# LoRa_1W_Breakout_868MHz.net
KiCad netlist of a schematic drawn in EAGLE
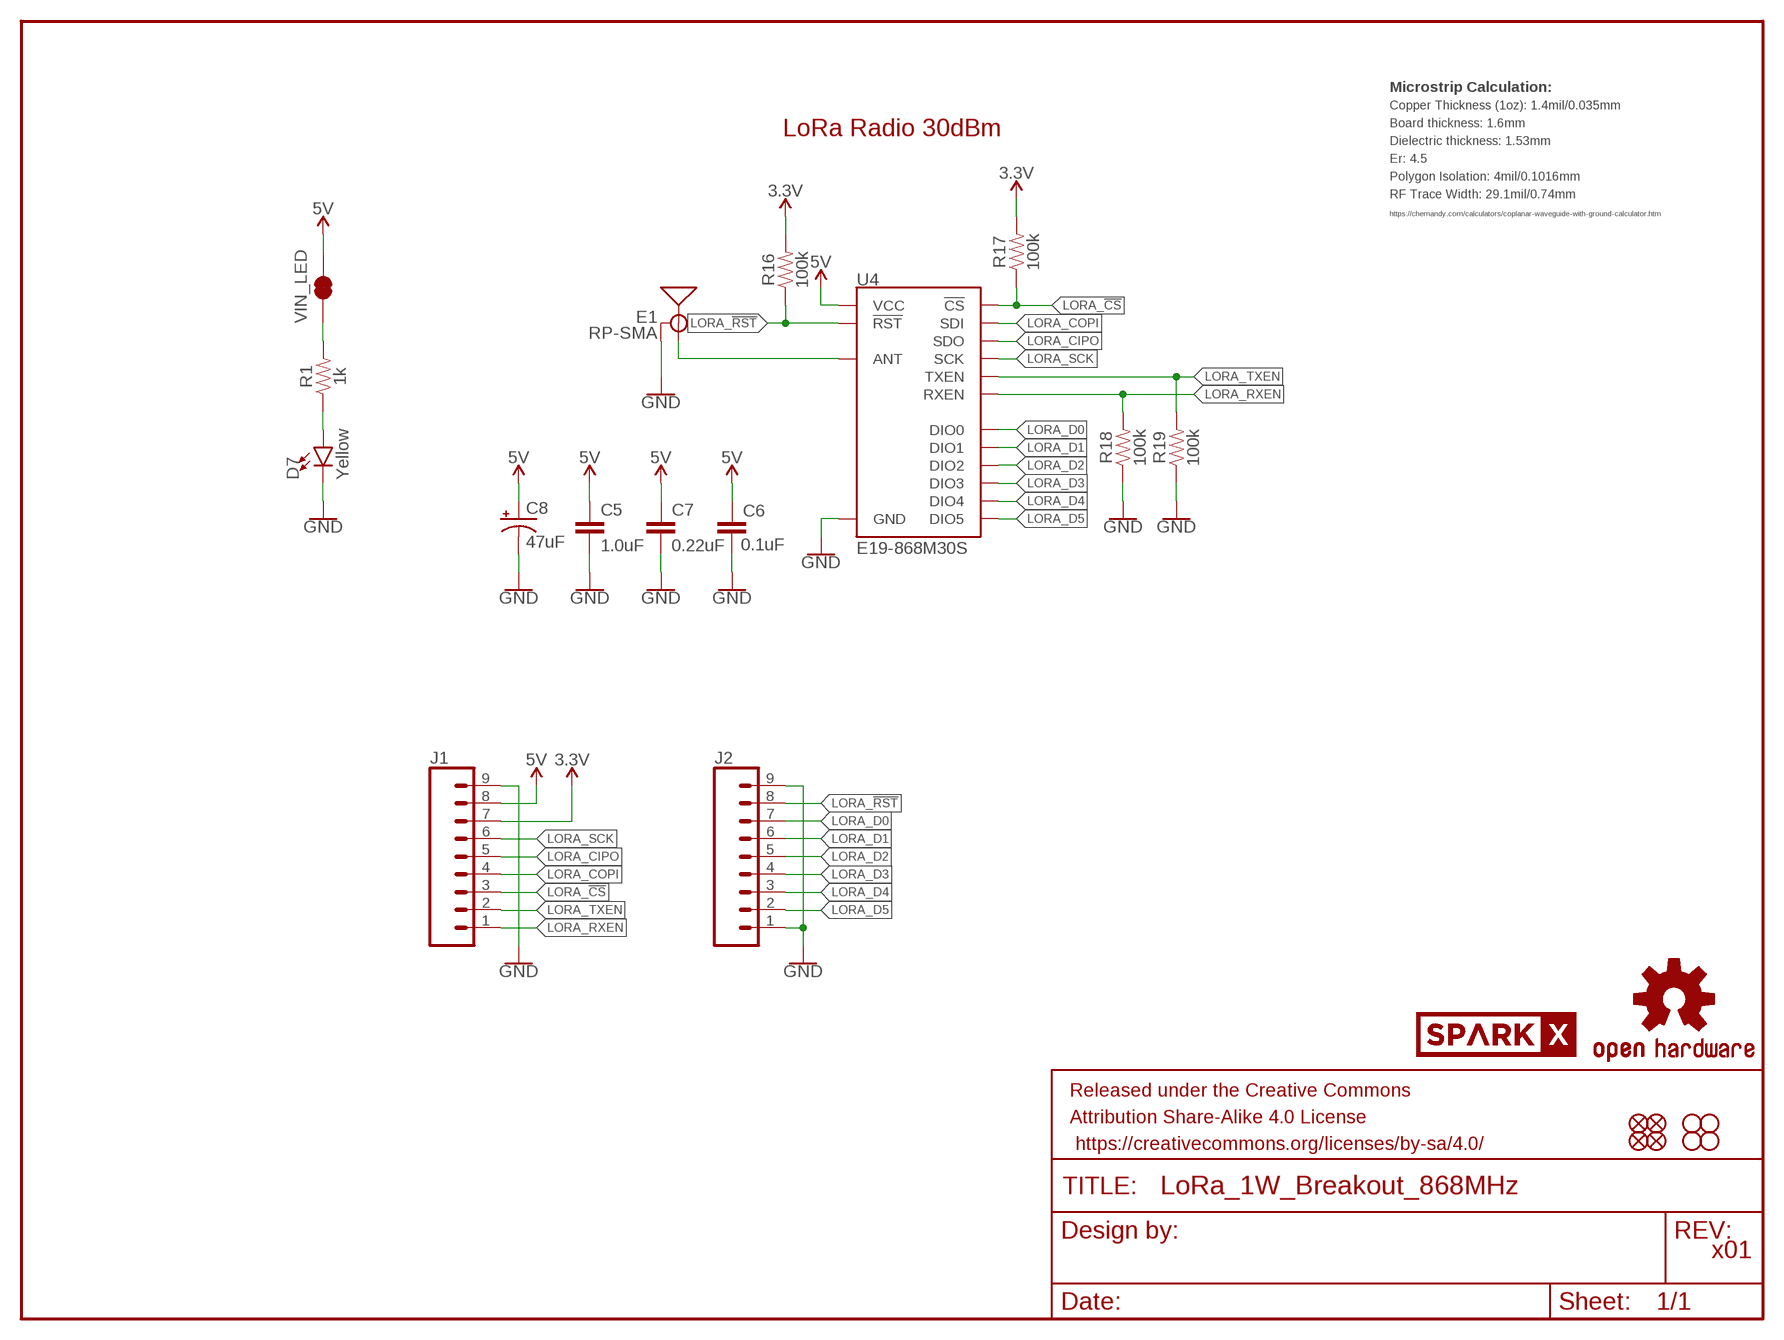
[diagram p0: schematic, sheet 1]

(export (version "E")
  (design (tool "Eeschema 10.0.6"))
  (components
    (comp (ref "C5")
      (value "1.0uF")
      (footprint "eagle-import:0603")
      (libsource (lib "eagle-import") (part "1.0UF-0603-16V-10%"))
    )
    (comp (ref "C6")
      (value "0.1uF")
      (footprint "eagle-import:0603")
      (libsource (lib "eagle-import") (part "0.1UF-0603-25V-(+80/-20%)"))
    )
    (comp (ref "C7")
      (value "0.22uF")
      (footprint "eagle-import:0603")
      (libsource (lib "eagle-import") (part "0.22UF-0603-25V-10%"))
    )
    (comp (ref "C8")
      (value "47uF")
      (footprint "eagle-import:EIA3528")
      (libsource (lib "eagle-import") (part "47UF-POLAR-EIA3528-10V-10%"))
    )
    (comp (ref "D7")
      (value "Yellow")
      (footprint "eagle-import:LED-0603")
      (libsource (lib "eagle-import") (part "LED-YELLOW0603"))
    )
    (comp (ref "E1")
      (value "RP-SMA")
      (footprint "eagle-import:SMA-EDGE")
      (libsource (lib "eagle-import") (part "ANTENNA-SMA-GROUNDEDEDGE_RPSMA"))
    )
    (comp (ref "FD1")
      (value "FIDUCIALUFIDUCIAL")
      (footprint "eagle-import:FIDUCIAL-MICRO")
      (libsource (lib "eagle-import") (part "FIDUCIALUFIDUCIAL"))
    )
    (comp (ref "FD2")
      (value "FIDUCIALUFIDUCIAL")
      (footprint "eagle-import:FIDUCIAL-MICRO")
      (libsource (lib "eagle-import") (part "FIDUCIALUFIDUCIAL"))
    )
    (comp (ref "FD3")
      (value "FIDUCIALUFIDUCIAL")
      (footprint "eagle-import:FIDUCIAL-MICRO")
      (libsource (lib "eagle-import") (part "FIDUCIALUFIDUCIAL"))
    )
    (comp (ref "FD4")
      (value "FIDUCIALUFIDUCIAL")
      (footprint "eagle-import:FIDUCIAL-MICRO")
      (libsource (lib "eagle-import") (part "FIDUCIALUFIDUCIAL"))
    )
    (comp (ref "FRAME2")
      (value "FRAME-LETTER")
      (footprint "eagle-import:CREATIVE_COMMONS")
      (libsource (lib "eagle-import") (part "FRAME-LETTER"))
    )
    (comp (ref "H1")
      (value "STAND-OFF")
      (footprint "eagle-import:STAND-OFF")
      (libsource (lib "eagle-import") (part "STAND-OFF"))
    )
    (comp (ref "H2")
      (value "STAND-OFF")
      (footprint "eagle-import:STAND-OFF")
      (libsource (lib "eagle-import") (part "STAND-OFF"))
    )
    (comp (ref "H3")
      (value "STAND-OFF")
      (footprint "eagle-import:STAND-OFF")
      (libsource (lib "eagle-import") (part "STAND-OFF"))
    )
    (comp (ref "H4")
      (value "STAND-OFF")
      (footprint "eagle-import:STAND-OFF")
      (libsource (lib "eagle-import") (part "STAND-OFF"))
    )
    (comp (ref "J1")
      (value "CONN_09NO_SILK")
      (footprint "eagle-import:1X09_NO_SILK")
      (libsource (lib "eagle-import") (part "CONN_09NO_SILK"))
    )
    (comp (ref "J2")
      (value "CONN_09NO_SILK")
      (footprint "eagle-import:1X09_NO_SILK")
      (libsource (lib "eagle-import") (part "CONN_09NO_SILK"))
    )
    (comp (ref "LOGO3")
      (value "OSHW-LOGOMINI")
      (footprint "eagle-import:OSHW-LOGO-MINI")
      (libsource (lib "eagle-import") (part "OSHW-LOGOMINI"))
    )
    (comp (ref "R1")
      (value "1k")
      (footprint "eagle-import:0603")
      (libsource (lib "eagle-import") (part "1KOHM-0603-1/10W-1%"))
    )
    (comp (ref "R16")
      (value "100k")
      (footprint "eagle-import:0603")
      (libsource (lib "eagle-import") (part "100KOHM-0603-1/10W-1%"))
    )
    (comp (ref "R17")
      (value "100k")
      (footprint "eagle-import:0603")
      (libsource (lib "eagle-import") (part "100KOHM-0603-1/10W-1%"))
    )
    (comp (ref "R18")
      (value "100k")
      (footprint "eagle-import:0603")
      (libsource (lib "eagle-import") (part "100KOHM-0603-1/10W-1%"))
    )
    (comp (ref "R19")
      (value "100k")
      (footprint "eagle-import:0603")
      (libsource (lib "eagle-import") (part "100KOHM-0603-1/10W-1%"))
    )
    (comp (ref "U$5")
      (value "SPARKX-LOGO5")
      (footprint "eagle-import:SPARKX-LARGE")
      (libsource (lib "eagle-import") (part "SPARKX-LOGO5"))
    )
    (comp (ref "U4")
      (value "E19-868M30S")
      (footprint "eagle-import:E19-915M30S")
      (libsource (lib "eagle-import") (part "LORA-E19868MHZ"))
    )
    (comp (ref "VIN_LED")
      (value "JUMPER-SMT_2_NC_TRACE_SILK")
      (footprint "eagle-import:SMT-JUMPER_2_NC_TRACE_SILK")
      (libsource (lib "eagle-import") (part "JUMPER-SMT_2_NC_TRACE_SILK"))
    )
  )
  (nets
    (net (code "1") (name "/LORA_~{CS}") (class "Default")
      (node (ref "J1") (pin "3") (pinfunction "3_3") (pintype "passive"))
      (node (ref "R17") (pin "1") (pinfunction "1_1") (pintype "passive"))
      (node (ref "U4") (pin "15") (pinfunction "~{CS}_15") (pintype "bidirectional"))
    )
    (net (code "2") (name "/LORA_~{RST}") (class "Default")
      (node (ref "J2") (pin "8") (pinfunction "8_8") (pintype "passive"))
      (node (ref "R16") (pin "1") (pinfunction "1_1") (pintype "passive"))
      (node (ref "U4") (pin "8") (pinfunction "~{RST}_8") (pintype "bidirectional"))
    )
    (net (code "3") (name "3.3V") (class "Default")
      (node (ref "J1") (pin "7") (pinfunction "7_7") (pintype "passive"))
      (node (ref "R16") (pin "2") (pinfunction "2_2") (pintype "passive"))
      (node (ref "R17") (pin "2") (pinfunction "2_2") (pintype "passive"))
    )
    (net (code "4") (name "5V") (class "Default")
      (node (ref "C5") (pin "1") (pinfunction "1_1") (pintype "passive"))
      (node (ref "C6") (pin "1") (pinfunction "1_1") (pintype "passive"))
      (node (ref "C7") (pin "1") (pinfunction "1_1") (pintype "passive"))
      (node (ref "C8") (pin "A") (pinfunction "+_A") (pintype "passive"))
      (node (ref "J1") (pin "8") (pinfunction "8_8") (pintype "passive"))
      (node (ref "U4") (pin "11") (pinfunction "VCC_11") (pintype "bidirectional"))
      (node (ref "VIN_LED") (pin "2") (pinfunction "2_2") (pintype "passive"))
    )
    (net (code "5") (name "GND") (class "Default")
      (node (ref "C5") (pin "2") (pinfunction "2_2") (pintype "passive"))
      (node (ref "C6") (pin "2") (pinfunction "2_2") (pintype "passive"))
      (node (ref "C7") (pin "2") (pinfunction "2_2") (pintype "passive"))
      (node (ref "C8") (pin "C") (pinfunction "-_C") (pintype "passive"))
      (node (ref "D7") (pin "C") (pinfunction "C_C") (pintype "passive"))
      (node (ref "E1") (pin "GND@0") (pinfunction "GND_GND@0") (pintype "bidirectional"))
      (node (ref "E1") (pin "GND@1") (pinfunction "GND_GND@1") (pintype "bidirectional"))
      (node (ref "E1") (pin "GND@2") (pinfunction "GND_GND@2") (pintype "bidirectional"))
      (node (ref "E1") (pin "GND@3") (pinfunction "GND_GND@3") (pintype "bidirectional"))
      (node (ref "J1") (pin "9") (pinfunction "9_9") (pintype "passive"))
      (node (ref "J2") (pin "1") (pinfunction "1_1") (pintype "passive"))
      (node (ref "J2") (pin "9") (pinfunction "9_9") (pintype "passive"))
      (node (ref "R18") (pin "1") (pinfunction "1_1") (pintype "passive"))
      (node (ref "R19") (pin "1") (pinfunction "1_1") (pintype "passive"))
      (node (ref "U4") (pin "1") (pinfunction "GND_1") (pintype "bidirectional"))
      (node (ref "U4") (pin "10") (pinfunction "GND_10") (pintype "bidirectional"))
      (node (ref "U4") (pin "18") (pinfunction "GND_18") (pintype "bidirectional"))
      (node (ref "U4") (pin "20") (pinfunction "GND_20") (pintype "bidirectional"))
      (node (ref "U4") (pin "21") (pinfunction "GND_21") (pintype "bidirectional"))
      (node (ref "U4") (pin "22") (pinfunction "GND_22") (pintype "bidirectional"))
      (node (ref "U4") (pin "9") (pinfunction "GND_9") (pintype "bidirectional"))
    )
    (net (code "6") (name "LORA_CIPO") (class "Default")
      (node (ref "J1") (pin "5") (pinfunction "5_5") (pintype "passive"))
      (node (ref "U4") (pin "13") (pinfunction "SDO_13") (pintype "bidirectional"))
    )
    (net (code "7") (name "LORA_COPI") (class "Default")
      (node (ref "J1") (pin "4") (pinfunction "4_4") (pintype "passive"))
      (node (ref "U4") (pin "14") (pinfunction "SDI_14") (pintype "bidirectional"))
    )
    (net (code "8") (name "LORA_D0") (class "Default")
      (node (ref "J2") (pin "7") (pinfunction "7_7") (pintype "passive"))
      (node (ref "U4") (pin "7") (pinfunction "DIO0_7") (pintype "bidirectional"))
    )
    (net (code "9") (name "LORA_D1") (class "Default")
      (node (ref "J2") (pin "6") (pinfunction "6_6") (pintype "passive"))
      (node (ref "U4") (pin "6") (pinfunction "DIO1_6") (pintype "bidirectional"))
    )
    (net (code "10") (name "LORA_D2") (class "Default")
      (node (ref "J2") (pin "5") (pinfunction "5_5") (pintype "passive"))
      (node (ref "U4") (pin "5") (pinfunction "DIO2_5") (pintype "bidirectional"))
    )
    (net (code "11") (name "LORA_D3") (class "Default")
      (node (ref "J2") (pin "4") (pinfunction "4_4") (pintype "passive"))
      (node (ref "U4") (pin "4") (pinfunction "DIO3_4") (pintype "bidirectional"))
    )
    (net (code "12") (name "LORA_D4") (class "Default")
      (node (ref "J2") (pin "3") (pinfunction "3_3") (pintype "passive"))
      (node (ref "U4") (pin "3") (pinfunction "DIO4_3") (pintype "bidirectional"))
    )
    (net (code "13") (name "LORA_D5") (class "Default")
      (node (ref "J2") (pin "2") (pinfunction "2_2") (pintype "passive"))
      (node (ref "U4") (pin "2") (pinfunction "DIO5_2") (pintype "bidirectional"))
    )
    (net (code "14") (name "LORA_RXEN") (class "Default")
      (node (ref "J1") (pin "1") (pinfunction "1_1") (pintype "passive"))
      (node (ref "R18") (pin "2") (pinfunction "2_2") (pintype "passive"))
      (node (ref "U4") (pin "17") (pinfunction "RXEN_17") (pintype "bidirectional"))
    )
    (net (code "15") (name "LORA_SCK") (class "Default")
      (node (ref "J1") (pin "6") (pinfunction "6_6") (pintype "passive"))
      (node (ref "U4") (pin "12") (pinfunction "SCK_12") (pintype "bidirectional"))
    )
    (net (code "16") (name "LORA_TXEN") (class "Default")
      (node (ref "J1") (pin "2") (pinfunction "2_2") (pintype "passive"))
      (node (ref "R19") (pin "2") (pinfunction "2_2") (pintype "passive"))
      (node (ref "U4") (pin "16") (pinfunction "TXEN_16") (pintype "bidirectional"))
    )
    (net (code "17") (name "Net-(D7-PadA)") (class "Default")
      (node (ref "D7") (pin "A") (pinfunction "A_A") (pintype "passive"))
      (node (ref "R1") (pin "1") (pinfunction "1_1") (pintype "passive"))
    )
    (net (code "18") (name "Net-(E1-SIGNAL)") (class "Default")
      (node (ref "E1") (pin "SIG") (pinfunction "SIGNAL_SIG") (pintype "bidirectional"))
      (node (ref "U4") (pin "19") (pinfunction "ANT_19") (pintype "bidirectional"))
    )
    (net (code "19") (name "Net-(R1-Pad2)") (class "Default")
      (node (ref "R1") (pin "2") (pinfunction "2_2") (pintype "passive"))
      (node (ref "VIN_LED") (pin "1") (pinfunction "1_1") (pintype "passive"))
    )
  )
)
